# LED-PCB_DIG3.net
KiCad netlist of a schematic drawn in Altium Designer
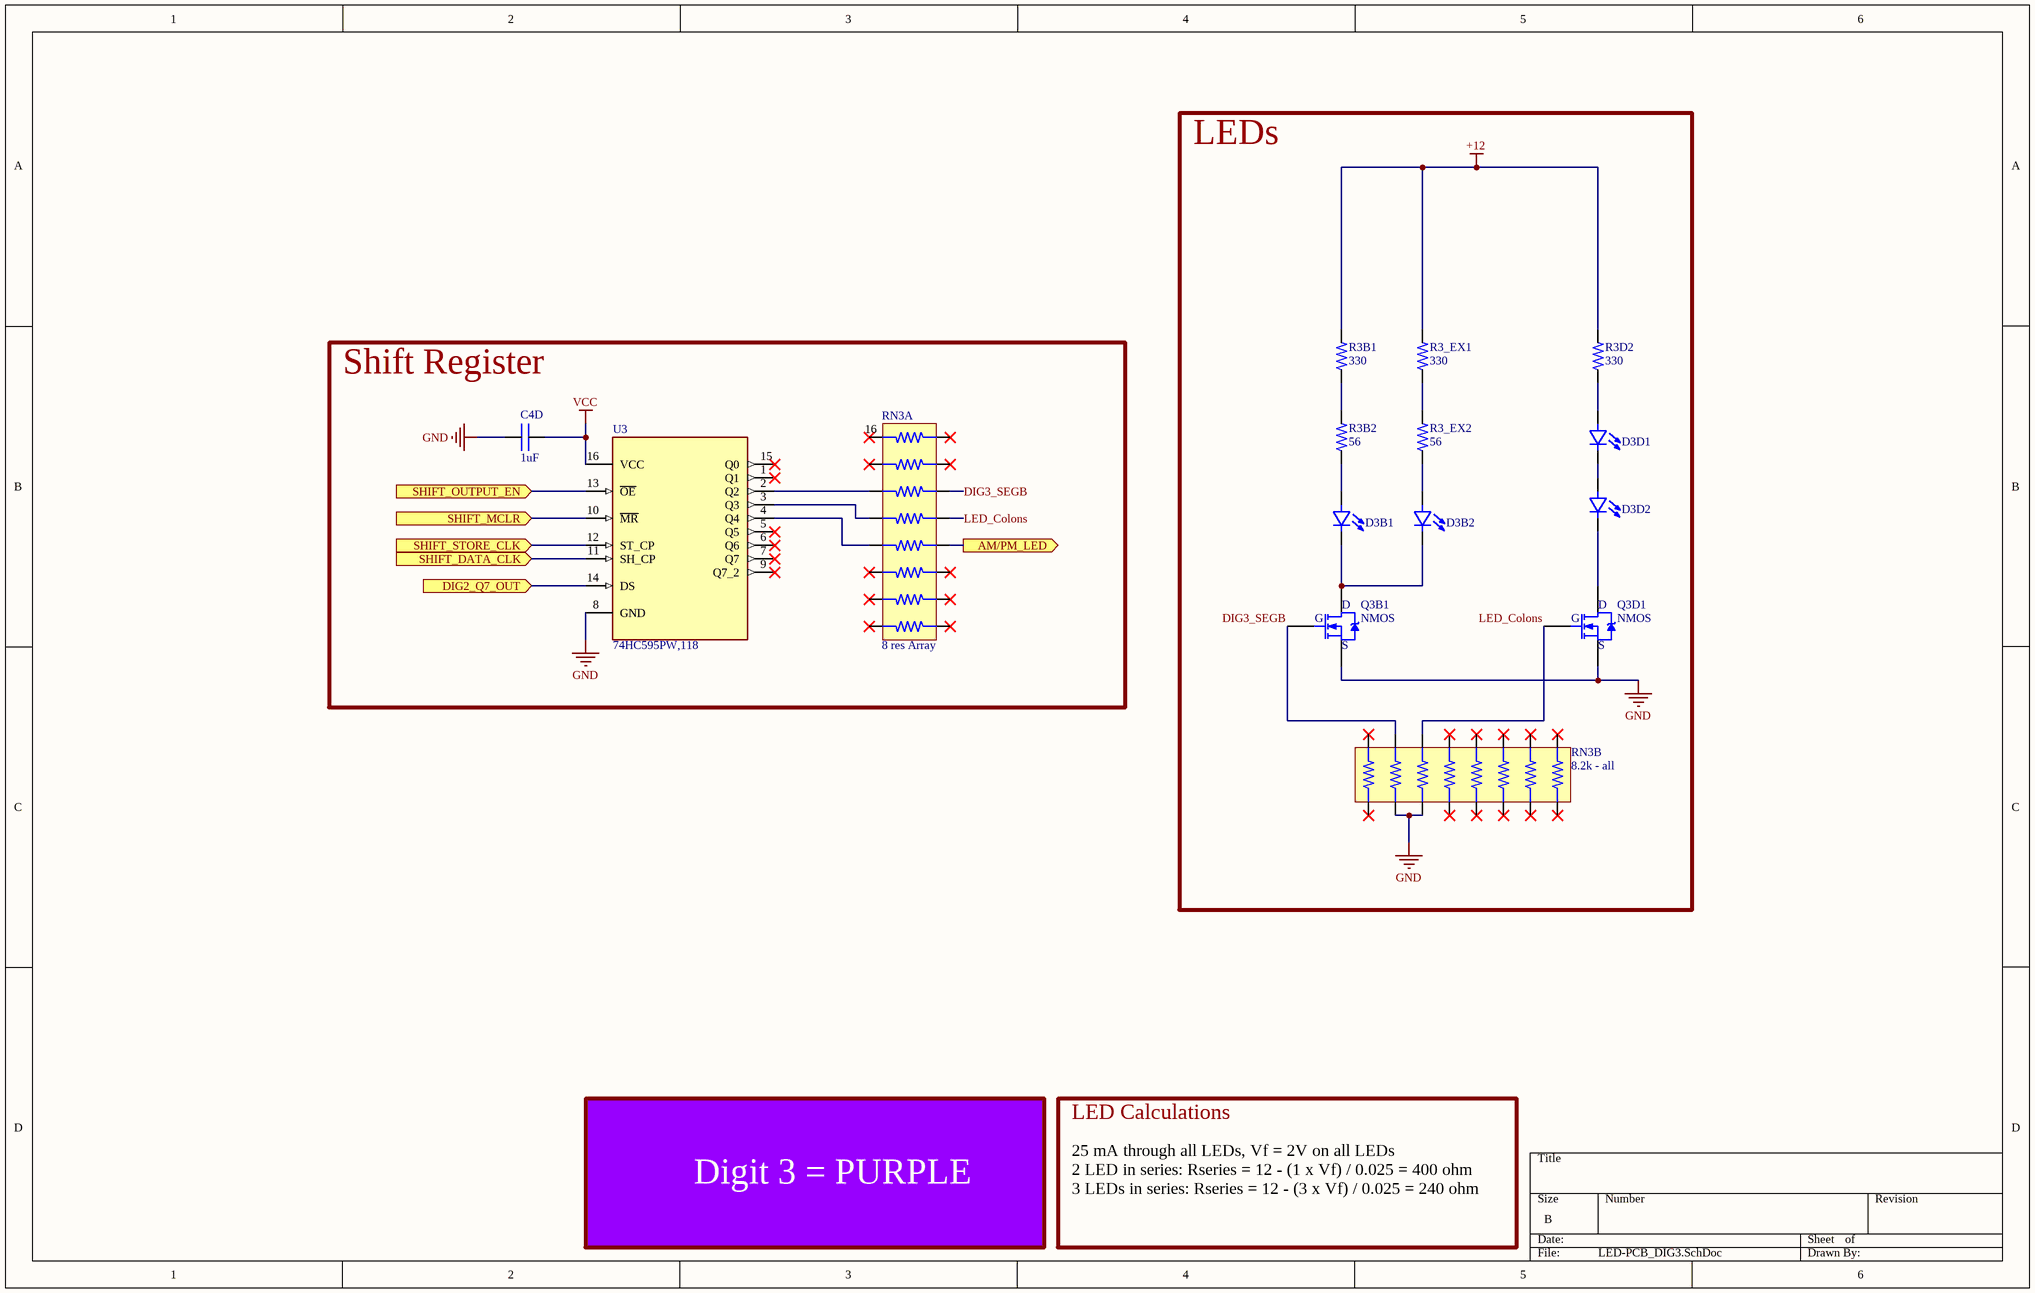
[diagram p0: LED-PCB_DIG3.SchDoc]

(export (version "E")
  (design (tool "Eeschema 10.0.6"))
  (components
    (comp (ref "C4D")
      (value "1uF")
      (footprint "sinking-clock:0402 CAP")
      (description "Capaicitor")
      (fields (field (name "MFR") "Samsung Microelectronics") (field (name "Comment") "CAP"))
      (libsource (lib "sinking-clock") (part "CAP"))
    )
    (comp (ref "D3B1")
      (value "LED - single")
      (footprint "sinking-clock:LED - 0603")
      (fields (field (name "MFR") "Wurth Elektronik"))
      (libsource (lib "sinking-clock") (part "LED - single"))
    )
    (comp (ref "D3B2")
      (value "LED - single")
      (footprint "sinking-clock:LED - 0603")
      (fields (field (name "MFR") "Wurth Elektronik"))
      (libsource (lib "sinking-clock") (part "LED - single"))
    )
    (comp (ref "D3D1")
      (value "LED - single")
      (footprint "sinking-clock:LED - 0603")
      (fields (field (name "MFR") "Wurth Elektronik"))
      (libsource (lib "sinking-clock") (part "LED - single"))
    )
    (comp (ref "D3D2")
      (value "LED - single")
      (footprint "sinking-clock:LED - 0603")
      (fields (field (name "MFR") "Wurth Elektronik"))
      (libsource (lib "sinking-clock") (part "LED - single"))
    )
    (comp (ref "Q3B1")
      (value "NMOS")
      (footprint "sinking-clock:SOT-23")
      (description "N-Channel MOSFET")
      (fields (field (name "MFR") "Diodes Incorporated"))
      (libsource (lib "sinking-clock") (part "NMOS"))
    )
    (comp (ref "Q3D1")
      (value "NMOS")
      (footprint "sinking-clock:SOT-23")
      (description "N-Channel MOSFET")
      (fields (field (name "MFR") "Diodes Incorporated"))
      (libsource (lib "sinking-clock") (part "NMOS"))
    )
    (comp (ref "R3B1")
      (value "330")
      (footprint "sinking-clock:0402 RES")
      (description "Resistor")
      (fields (field (name "MFR") "YAGEO") (field (name "Comment") "RES"))
      (libsource (lib "sinking-clock") (part "RES"))
    )
    (comp (ref "R3B2")
      (value "56")
      (footprint "sinking-clock:0402 RES")
      (description "Resistor")
      (fields (field (name "MFR") "YAGEO") (field (name "Comment") "RES"))
      (libsource (lib "sinking-clock") (part "RES"))
    )
    (comp (ref "R3D2")
      (value "330")
      (footprint "sinking-clock:0402 RES")
      (description "Resistor")
      (fields (field (name "MFR") "YAGEO") (field (name "Comment") "RES"))
      (libsource (lib "sinking-clock") (part "RES"))
    )
    (comp (ref "R3_EX1")
      (value "330")
      (footprint "sinking-clock:0402R")
      (description "Resistor")
      (fields (field (name "MFR") "YAGEO") (field (name "Comment") "RES"))
      (libsource (lib "sinking-clock") (part "RES"))
    )
    (comp (ref "R3_EX2")
      (value "56")
      (footprint "sinking-clock:0402R")
      (description "Resistor")
      (fields (field (name "MFR") "YAGEO") (field (name "Comment") "RES"))
      (libsource (lib "sinking-clock") (part "RES"))
    )
    (comp (ref "RN3A")
      (value "8 res Array")
      (footprint "sinking-clock:EXB2HV331JV")
      (fields (field (name "MFR") "Panasonic Microelectronics"))
      (libsource (lib "sinking-clock") (part "8 res Array"))
    )
    (comp (ref "RN3B")
      (value "8.2k - all")
      (footprint "sinking-clock:MNR18ERAPJ822")
      (fields (field (name "MFR") "Rohm Semiconductor"))
      (libsource (lib "sinking-clock") (part "MNR18ERAPJ822"))
    )
    (comp (ref "U3")
      (value "74HC595PW,118")
      (footprint "sinking-clock:16-TSSOP")
      (description "Shift Shift Register 1 Element 8 Bit 16-TSSOP")
      (libsource (lib "sinking-clock") (part "74HC595PW,118"))
    )
  )
  (nets
    (net (code "1") (name "+12") (class "Default")
      (node (ref "R3B1") (pin "2") (pinfunction "2_2") (pintype "passive"))
      (node (ref "R3D2") (pin "2") (pinfunction "2_2") (pintype "passive"))
      (node (ref "R3_EX1") (pin "2") (pinfunction "2_2") (pintype "passive"))
    )
    (net (code "2") (name "/AM{slash}PM_LED") (class "Default")
      (node (ref "RN3A") (pin "5") (pinfunction "5_5") (pintype "passive"))
    )
    (net (code "3") (name "/DIG2_Q7_OUT") (class "Default")
      (node (ref "U3") (pin "14") (pinfunction "DS_14") (pintype "input"))
    )
    (net (code "4") (name "/DIG3_SEGB") (class "Default")
      (node (ref "Q3B1") (pin "1") (pinfunction "G_1") (pintype "passive"))
      (node (ref "RN3A") (pin "3") (pinfunction "3_3") (pintype "passive"))
      (node (ref "RN3B") (pin "15") (pinfunction "15_15") (pintype "passive"))
    )
    (net (code "5") (name "/LED_Colons") (class "Default")
      (node (ref "Q3D1") (pin "1") (pinfunction "G_1") (pintype "passive"))
      (node (ref "RN3A") (pin "4") (pinfunction "4_4") (pintype "passive"))
      (node (ref "RN3B") (pin "14") (pinfunction "14_14") (pintype "passive"))
    )
    (net (code "6") (name "/SHIFT_DATA_CLK") (class "Default")
      (node (ref "U3") (pin "11") (pinfunction "SH_CP_11") (pintype "input"))
    )
    (net (code "7") (name "/SHIFT_MCLR") (class "Default")
      (node (ref "U3") (pin "10") (pinfunction "~{MR}_10") (pintype "input"))
    )
    (net (code "8") (name "/SHIFT_OUTPUT_EN") (class "Default")
      (node (ref "U3") (pin "13") (pinfunction "~{OE}_13") (pintype "input"))
    )
    (net (code "9") (name "/SHIFT_STORE_CLK") (class "Default")
      (node (ref "U3") (pin "12") (pinfunction "ST_CP_12") (pintype "input"))
    )
    (net (code "10") (name "GND") (class "Default")
      (node (ref "C4D") (pin "2") (pinfunction "2_2") (pintype "passive"))
      (node (ref "Q3B1") (pin "2") (pinfunction "S_2") (pintype "passive"))
      (node (ref "Q3D1") (pin "2") (pinfunction "S_2") (pintype "passive"))
      (node (ref "RN3B") (pin "2") (pinfunction "2_2") (pintype "passive"))
      (node (ref "RN3B") (pin "3") (pinfunction "3_3") (pintype "passive"))
      (node (ref "U3") (pin "8") (pinfunction "GND_8") (pintype "passive"))
    )
    (net (code "11") (name "Net-(D3B1-A)") (class "Default")
      (node (ref "D3B1") (pin "1") (pinfunction "A_1") (pintype "passive"))
      (node (ref "R3B2") (pin "1") (pinfunction "1_1") (pintype "passive"))
    )
    (net (code "12") (name "Net-(D3B1-C)") (class "Default")
      (node (ref "D3B1") (pin "2") (pinfunction "C_2") (pintype "passive"))
      (node (ref "D3B2") (pin "2") (pinfunction "C_2") (pintype "passive"))
      (node (ref "Q3B1") (pin "3") (pinfunction "D_3") (pintype "passive"))
    )
    (net (code "13") (name "Net-(D3B2-A)") (class "Default")
      (node (ref "D3B2") (pin "1") (pinfunction "A_1") (pintype "passive"))
      (node (ref "R3_EX2") (pin "1") (pinfunction "1_1") (pintype "passive"))
    )
    (net (code "14") (name "Net-(D3D1-A)") (class "Default")
      (node (ref "D3D1") (pin "1") (pinfunction "A_1") (pintype "passive"))
      (node (ref "R3D2") (pin "1") (pinfunction "1_1") (pintype "passive"))
    )
    (net (code "15") (name "Net-(D3D1-C)") (class "Default")
      (node (ref "D3D1") (pin "2") (pinfunction "C_2") (pintype "passive"))
      (node (ref "D3D2") (pin "1") (pinfunction "A_1") (pintype "passive"))
    )
    (net (code "16") (name "Net-(D3D2-C)") (class "Default")
      (node (ref "D3D2") (pin "2") (pinfunction "C_2") (pintype "passive"))
      (node (ref "Q3D1") (pin "3") (pinfunction "D_3") (pintype "passive"))
    )
    (net (code "17") (name "Net-(R3B1-Pad1)") (class "Default")
      (node (ref "R3B1") (pin "1") (pinfunction "1_1") (pintype "passive"))
      (node (ref "R3B2") (pin "2") (pinfunction "2_2") (pintype "passive"))
    )
    (net (code "18") (name "Net-(R3_EX1-Pad1)") (class "Default")
      (node (ref "R3_EX1") (pin "1") (pinfunction "1_1") (pintype "passive"))
      (node (ref "R3_EX2") (pin "2") (pinfunction "2_2") (pintype "passive"))
    )
    (net (code "19") (name "Net-(U3-Q2)") (class "Default")
      (node (ref "RN3A") (pin "14") (pinfunction "14_14") (pintype "passive"))
      (node (ref "U3") (pin "2") (pinfunction "Q2_2") (pintype "output"))
    )
    (net (code "20") (name "Net-(U3-Q3)") (class "Default")
      (node (ref "RN3A") (pin "13") (pinfunction "13_13") (pintype "passive"))
      (node (ref "U3") (pin "3") (pinfunction "Q3_3") (pintype "output"))
    )
    (net (code "21") (name "Net-(U3-Q4)") (class "Default")
      (node (ref "RN3A") (pin "12") (pinfunction "12_12") (pintype "passive"))
      (node (ref "U3") (pin "4") (pinfunction "Q4_4") (pintype "output"))
    )
    (net (code "22") (name "VCC") (class "Default")
      (node (ref "C4D") (pin "1") (pinfunction "1_1") (pintype "passive"))
      (node (ref "U3") (pin "16") (pinfunction "VCC_16") (pintype "power_in"))
    )
    (net (code "23") (name "unconnected-(RN3A-Pad1)") (class "Default")
      (node (ref "RN3A") (pin "1") (pinfunction "1_1") (pintype "passive+no_connect"))
    )
    (net (code "24") (name "unconnected-(RN3A-Pad2)") (class "Default")
      (node (ref "RN3A") (pin "2") (pinfunction "2_2") (pintype "passive+no_connect"))
    )
    (net (code "25") (name "unconnected-(RN3A-Pad6)") (class "Default")
      (node (ref "RN3A") (pin "6") (pinfunction "6_6") (pintype "passive+no_connect"))
    )
    (net (code "26") (name "unconnected-(RN3A-Pad7)") (class "Default")
      (node (ref "RN3A") (pin "7") (pinfunction "7_7") (pintype "passive+no_connect"))
    )
    (net (code "27") (name "unconnected-(RN3A-Pad8)") (class "Default")
      (node (ref "RN3A") (pin "8") (pinfunction "8_8") (pintype "passive+no_connect"))
    )
    (net (code "28") (name "unconnected-(RN3A-Pad9)") (class "Default")
      (node (ref "RN3A") (pin "9") (pinfunction "9_9") (pintype "passive+no_connect"))
    )
    (net (code "29") (name "unconnected-(RN3A-Pad10)") (class "Default")
      (node (ref "RN3A") (pin "10") (pinfunction "10_10") (pintype "passive+no_connect"))
    )
    (net (code "30") (name "unconnected-(RN3A-Pad11)") (class "Default")
      (node (ref "RN3A") (pin "11") (pinfunction "11_11") (pintype "passive+no_connect"))
    )
    (net (code "31") (name "unconnected-(RN3A-Pad15)") (class "Default")
      (node (ref "RN3A") (pin "15") (pinfunction "15_15") (pintype "passive+no_connect"))
    )
    (net (code "32") (name "unconnected-(RN3A-Pad16)") (class "Default")
      (node (ref "RN3A") (pin "16") (pinfunction "16_16") (pintype "passive+no_connect"))
    )
    (net (code "33") (name "unconnected-(RN3B-Pad1)") (class "Default")
      (node (ref "RN3B") (pin "1") (pinfunction "1_1") (pintype "passive+no_connect"))
    )
    (net (code "34") (name "unconnected-(RN3B-Pad4)") (class "Default")
      (node (ref "RN3B") (pin "4") (pinfunction "4_4") (pintype "passive+no_connect"))
    )
    (net (code "35") (name "unconnected-(RN3B-Pad5)") (class "Default")
      (node (ref "RN3B") (pin "5") (pinfunction "5_5") (pintype "passive+no_connect"))
    )
    (net (code "36") (name "unconnected-(RN3B-Pad6)") (class "Default")
      (node (ref "RN3B") (pin "6") (pinfunction "6_6") (pintype "passive+no_connect"))
    )
    (net (code "37") (name "unconnected-(RN3B-Pad7)") (class "Default")
      (node (ref "RN3B") (pin "7") (pinfunction "7_7") (pintype "passive+no_connect"))
    )
    (net (code "38") (name "unconnected-(RN3B-Pad8)") (class "Default")
      (node (ref "RN3B") (pin "8") (pinfunction "8_8") (pintype "passive+no_connect"))
    )
    (net (code "39") (name "unconnected-(RN3B-Pad9)") (class "Default")
      (node (ref "RN3B") (pin "9") (pinfunction "9_9") (pintype "passive+no_connect"))
    )
    (net (code "40") (name "unconnected-(RN3B-Pad10)") (class "Default")
      (node (ref "RN3B") (pin "10") (pinfunction "10_10") (pintype "passive+no_connect"))
    )
    (net (code "41") (name "unconnected-(RN3B-Pad11)") (class "Default")
      (node (ref "RN3B") (pin "11") (pinfunction "11_11") (pintype "passive+no_connect"))
    )
    (net (code "42") (name "unconnected-(RN3B-Pad12)") (class "Default")
      (node (ref "RN3B") (pin "12") (pinfunction "12_12") (pintype "passive+no_connect"))
    )
    (net (code "43") (name "unconnected-(RN3B-Pad13)") (class "Default")
      (node (ref "RN3B") (pin "13") (pinfunction "13_13") (pintype "passive+no_connect"))
    )
    (net (code "44") (name "unconnected-(RN3B-Pad16)") (class "Default")
      (node (ref "RN3B") (pin "16") (pinfunction "16_16") (pintype "passive+no_connect"))
    )
    (net (code "45") (name "unconnected-(U3-Q0-Pad15)") (class "Default")
      (node (ref "U3") (pin "15") (pinfunction "Q0_15") (pintype "output+no_connect"))
    )
    (net (code "46") (name "unconnected-(U3-Q1-Pad1)") (class "Default")
      (node (ref "U3") (pin "1") (pinfunction "Q1_1") (pintype "output+no_connect"))
    )
    (net (code "47") (name "unconnected-(U3-Q5-Pad5)") (class "Default")
      (node (ref "U3") (pin "5") (pinfunction "Q5_5") (pintype "output+no_connect"))
    )
    (net (code "48") (name "unconnected-(U3-Q6-Pad6)") (class "Default")
      (node (ref "U3") (pin "6") (pinfunction "Q6_6") (pintype "output+no_connect"))
    )
    (net (code "49") (name "unconnected-(U3-Q7-Pad7)") (class "Default")
      (node (ref "U3") (pin "7") (pinfunction "Q7_7") (pintype "output+no_connect"))
    )
    (net (code "50") (name "unconnected-(U3-Q7_2-Pad9)") (class "Default")
      (node (ref "U3") (pin "9") (pinfunction "Q7_2_9") (pintype "output+no_connect"))
    )
  )
)
